# uc.net
KiCad netlist of a schematic drawn in Altium Designer
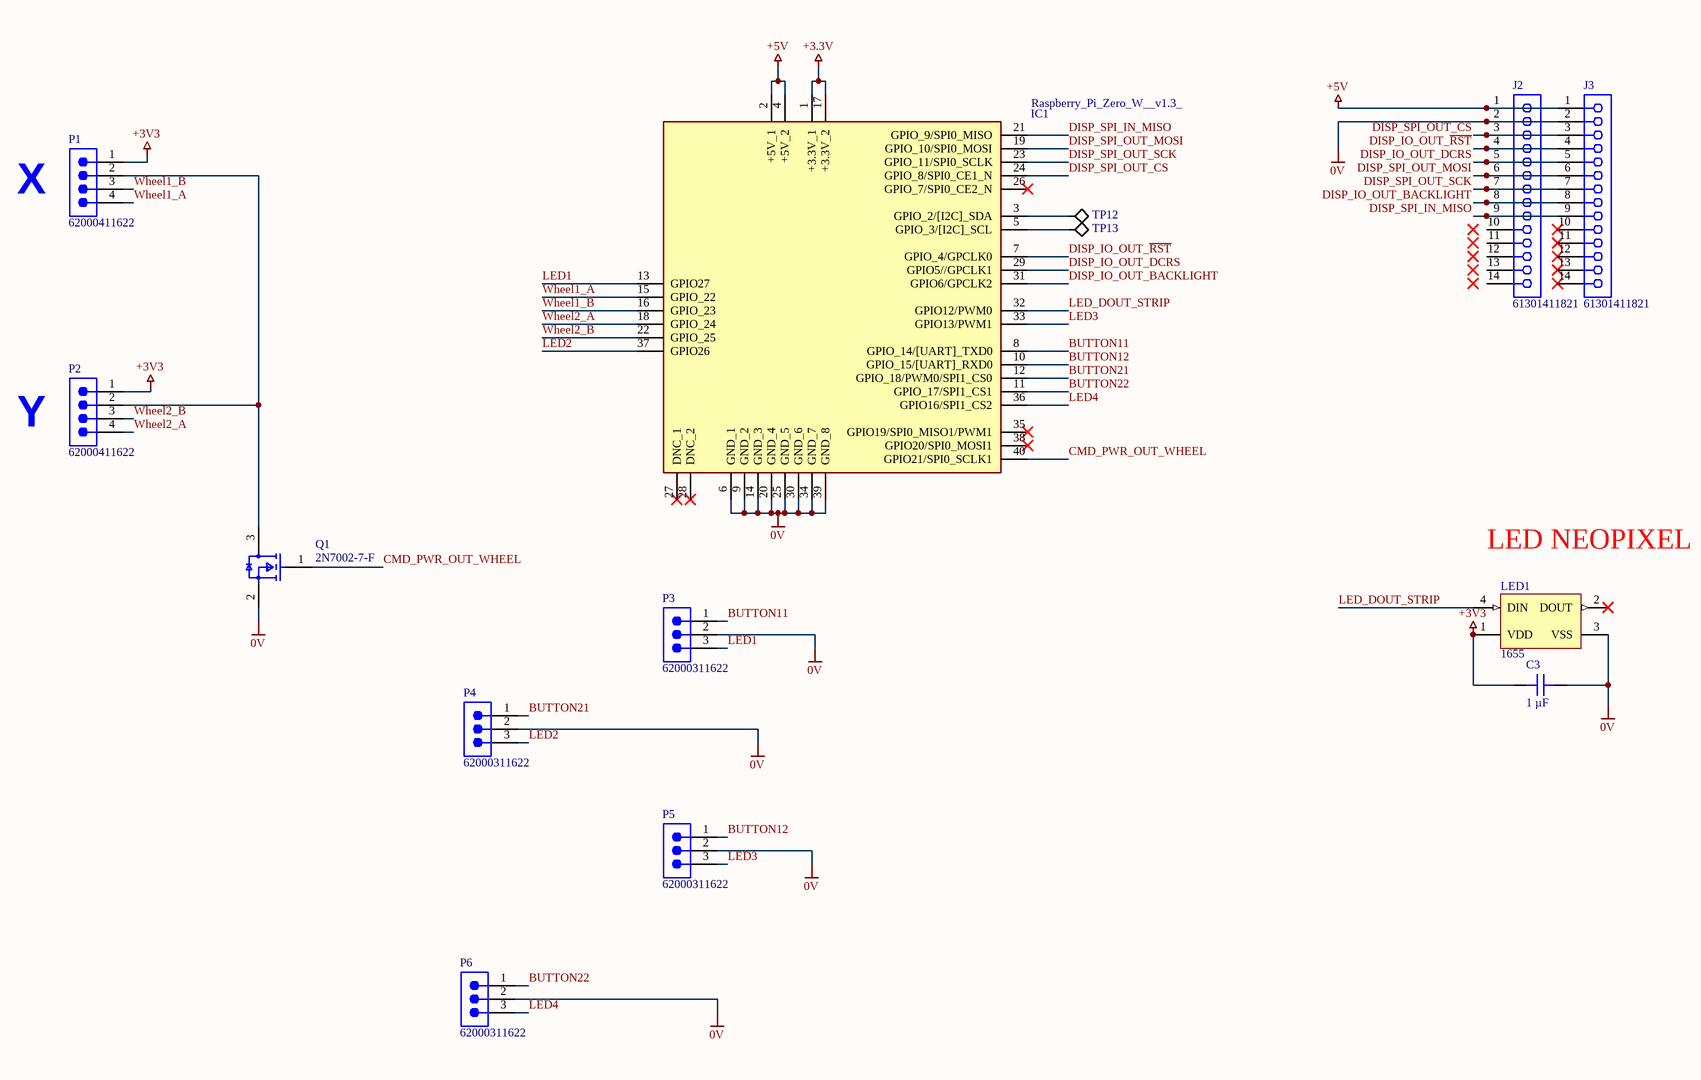
[diagram p0: uc.SchDoc]

(export (version "E")
  (design (tool "Eeschema 10.0.6"))
  (components
    (comp (ref "C3")
      (value "1 µF")
      (footprint "CAP 0603_1608")
      (description "CAP CER 1UF 16V X7R 0603")
      (fields
        (field (name "PART NUMBER") "GCM188R71C105KA64J")
        (field (name "MANUFACTURER") "Murata Electronics")
      )
      (libsource (lib "Celestial Altium Library - altium_library") (part "Capacitor"))
    )
    (comp (ref "IC1")
      (value "Raspberry_Pi_Zero_W__v1.3_")
      (footprint "RaspberryPiZero2W")
      (description "Integrated Circuit")
      (fields (field (name "MANUFACTURER_PART_NUMBER") "Raspberry Pi Zero W (v1.3)"))
      (libsource (lib "epieno") (part "Raspberry_Pi_Zero_W__v1.3_"))
    )
    (comp (ref "J2")
      (value "61301411821")
      (footprint "61301411821")
      (libsource (lib "Altium Content Vault") (part "Header_Female_1R_14P"))
    )
    (comp (ref "J3")
      (value "61301411821")
      (footprint "61301411821")
      (libsource (lib "Altium Content Vault") (part "Header_Female_1R_14P"))
    )
    (comp (ref "LED1")
      (value "1655")
      (footprint "ADA-RGB-1655_V")
      (fields (field (name "MANUFACTURER") "Adafruit-Industries-LLC"))
      (libsource (lib "Altium Content Vault") (part "ADA-RGB-1655-4"))
    )
    (comp (ref "P1")
      (value "62000411622")
      (footprint "62000411622")
      (libsource (lib "Altium Content Vault") (part "Header_Male_1R_04P"))
    )
    (comp (ref "P2")
      (value "62000411622")
      (footprint "62000411622")
      (libsource (lib "Altium Content Vault") (part "Header_Male_1R_04P"))
    )
    (comp (ref "P3")
      (value "62000311622")
      (footprint "62000311622")
      (libsource (lib "Altium Content Vault") (part "Header_Male_1R_03P"))
    )
    (comp (ref "P4")
      (value "62000311622")
      (footprint "62000311622")
      (libsource (lib "Altium Content Vault") (part "Header_Male_1R_03P"))
    )
    (comp (ref "P5")
      (value "62000311622")
      (footprint "62000311622")
      (libsource (lib "Altium Content Vault") (part "Header_Male_1R_03P"))
    )
    (comp (ref "P6")
      (value "62000311622")
      (footprint "62000311622")
      (libsource (lib "Altium Content Vault") (part "Header_Male_1R_03P"))
    )
    (comp (ref "Q1")
      (value "2N7002-7-F")
      (footprint "FP-SOT23-MFG")
      (description "MOSFET N-CH 60V 115MA SOT23-3")
      (fields (field (name "VOLTAGE") "60V"))
      (libsource (lib "Altium Content Vault") (part "3b9c635fedb024a5347a57b145af9cc"))
    )
    (comp (ref "TP12")
      (value "Test Point")
      (footprint "TESTPOINT_ROUND_2.0MM")
      (libsource (lib "epieno") (part "TEST_POINT_2MM"))
    )
    (comp (ref "TP13")
      (value "Test Point")
      (footprint "TESTPOINT_ROUND_2.0MM")
      (libsource (lib "epieno") (part "TEST_POINT_2MM"))
    )
  )
  (nets
    (net (code "1") (name "+3.3V") (class "Default")
      (node (ref "IC1") (pin "1") (pinfunction "+3.3V_1_1") (pintype "passive"))
      (node (ref "IC1") (pin "17") (pinfunction "+3.3V_2_17") (pintype "passive"))
    )
    (net (code "2") (name "+3V3") (class "Default")
      (node (ref "C3") (pin "2") (pinfunction "2_2") (pintype "passive"))
      (node (ref "LED1") (pin "1") (pinfunction "VDD_1") (pintype "power_in"))
      (node (ref "P1") (pin "1") (pinfunction "1_1") (pintype "passive"))
      (node (ref "P2") (pin "1") (pinfunction "1_1") (pintype "passive"))
    )
    (net (code "3") (name "+5V") (class "Default")
      (node (ref "IC1") (pin "2") (pinfunction "+5V_1_2") (pintype "passive"))
      (node (ref "IC1") (pin "4") (pinfunction "+5V_2_4") (pintype "passive"))
      (node (ref "J2") (pin "1") (pinfunction "1_1") (pintype "passive"))
      (node (ref "J3") (pin "1") (pinfunction "1_1") (pintype "passive"))
    )
    (net (code "4") (name "/BUTTON11") (class "Default")
      (node (ref "IC1") (pin "8") (pinfunction "GPIO_14/[UART]_TXD0_8") (pintype "passive"))
      (node (ref "P3") (pin "1") (pinfunction "1_1") (pintype "passive"))
    )
    (net (code "5") (name "/BUTTON12") (class "Default")
      (node (ref "IC1") (pin "10") (pinfunction "GPIO_15/[UART]_RXD0_10") (pintype "passive"))
      (node (ref "P5") (pin "1") (pinfunction "1_1") (pintype "passive"))
    )
    (net (code "6") (name "/BUTTON21") (class "Default")
      (node (ref "IC1") (pin "12") (pinfunction "GPIO_18/PWM0/SPI1_CS0_12") (pintype "passive"))
      (node (ref "P4") (pin "1") (pinfunction "1_1") (pintype "passive"))
    )
    (net (code "7") (name "/BUTTON22") (class "Default")
      (node (ref "IC1") (pin "11") (pinfunction "GPIO_17/SPI1_CS1_11") (pintype "passive"))
      (node (ref "P6") (pin "1") (pinfunction "1_1") (pintype "passive"))
    )
    (net (code "8") (name "/CMD_PWR_OUT_WHEEL") (class "Default")
      (node (ref "IC1") (pin "40") (pinfunction "GPIO21/SPI0_SCLK1_40") (pintype "passive"))
      (node (ref "Q1") (pin "1") (pinfunction "G_1") (pintype "passive"))
    )
    (net (code "9") (name "/DISP_IO_OUT_BACKLIGHT") (class "Default")
      (node (ref "IC1") (pin "31") (pinfunction "GPIO6/GPCLK2_31") (pintype "passive"))
      (node (ref "J2") (pin "8") (pinfunction "8_8") (pintype "passive"))
      (node (ref "J3") (pin "8") (pinfunction "8_8") (pintype "passive"))
    )
    (net (code "10") (name "/DISP_IO_OUT_DCRS") (class "Default")
      (node (ref "IC1") (pin "29") (pinfunction "GPIO5//GPCLK1_29") (pintype "passive"))
      (node (ref "J2") (pin "5") (pinfunction "5_5") (pintype "passive"))
      (node (ref "J3") (pin "5") (pinfunction "5_5") (pintype "passive"))
    )
    (net (code "11") (name "/DISP_IO_OUT_~{RST}") (class "Default")
      (node (ref "IC1") (pin "7") (pinfunction "GPIO_4/GPCLK0_7") (pintype "passive"))
      (node (ref "J2") (pin "4") (pinfunction "4_4") (pintype "passive"))
      (node (ref "J3") (pin "4") (pinfunction "4_4") (pintype "passive"))
    )
    (net (code "12") (name "/DISP_SPI_IN_MISO") (class "Default")
      (node (ref "IC1") (pin "21") (pinfunction "GPIO_9/SPI0_MISO_21") (pintype "passive"))
      (node (ref "J2") (pin "9") (pinfunction "9_9") (pintype "passive"))
      (node (ref "J3") (pin "9") (pinfunction "9_9") (pintype "passive"))
    )
    (net (code "13") (name "/DISP_SPI_OUT_CS") (class "Default")
      (node (ref "IC1") (pin "24") (pinfunction "GPIO_8/SPI0_CE1_N_24") (pintype "passive"))
      (node (ref "J2") (pin "3") (pinfunction "3_3") (pintype "passive"))
      (node (ref "J3") (pin "3") (pinfunction "3_3") (pintype "passive"))
    )
    (net (code "14") (name "/DISP_SPI_OUT_MOSI") (class "Default")
      (node (ref "IC1") (pin "19") (pinfunction "GPIO_10/SPI0_MOSI_19") (pintype "passive"))
      (node (ref "J2") (pin "6") (pinfunction "6_6") (pintype "passive"))
      (node (ref "J3") (pin "6") (pinfunction "6_6") (pintype "passive"))
    )
    (net (code "15") (name "/DISP_SPI_OUT_SCK") (class "Default")
      (node (ref "IC1") (pin "23") (pinfunction "GPIO_11/SPI0_SCLK_23") (pintype "passive"))
      (node (ref "J2") (pin "7") (pinfunction "7_7") (pintype "passive"))
      (node (ref "J3") (pin "7") (pinfunction "7_7") (pintype "passive"))
    )
    (net (code "16") (name "/LED1") (class "Default")
      (node (ref "IC1") (pin "13") (pinfunction "GPIO27_13") (pintype "passive"))
      (node (ref "P3") (pin "3") (pinfunction "3_3") (pintype "passive"))
    )
    (net (code "17") (name "/LED2") (class "Default")
      (node (ref "IC1") (pin "37") (pinfunction "GPIO26_37") (pintype "passive"))
      (node (ref "P4") (pin "3") (pinfunction "3_3") (pintype "passive"))
    )
    (net (code "18") (name "/LED3") (class "Default")
      (node (ref "IC1") (pin "33") (pinfunction "GPIO13/PWM1_33") (pintype "passive"))
      (node (ref "P5") (pin "3") (pinfunction "3_3") (pintype "passive"))
    )
    (net (code "19") (name "/LED4") (class "Default")
      (node (ref "IC1") (pin "36") (pinfunction "GPIO16/SPI1_CS2_36") (pintype "passive"))
      (node (ref "P6") (pin "3") (pinfunction "3_3") (pintype "passive"))
    )
    (net (code "20") (name "/LED_DOUT_STRIP") (class "Default")
      (node (ref "IC1") (pin "32") (pinfunction "GPIO12/PWM0_32") (pintype "passive"))
      (node (ref "LED1") (pin "4") (pinfunction "DIN_4") (pintype "input"))
    )
    (net (code "21") (name "/Wheel1_A") (class "Default")
      (node (ref "IC1") (pin "15") (pinfunction "GPIO_22_15") (pintype "passive"))
      (node (ref "P1") (pin "4") (pinfunction "4_4") (pintype "passive"))
    )
    (net (code "22") (name "/Wheel1_B") (class "Default")
      (node (ref "IC1") (pin "16") (pinfunction "GPIO_23_16") (pintype "passive"))
      (node (ref "P1") (pin "3") (pinfunction "3_3") (pintype "passive"))
    )
    (net (code "23") (name "/Wheel2_A") (class "Default")
      (node (ref "IC1") (pin "18") (pinfunction "GPIO_24_18") (pintype "passive"))
      (node (ref "P2") (pin "4") (pinfunction "4_4") (pintype "passive"))
    )
    (net (code "24") (name "/Wheel2_B") (class "Default")
      (node (ref "IC1") (pin "22") (pinfunction "GPIO_25_22") (pintype "passive"))
      (node (ref "P2") (pin "3") (pinfunction "3_3") (pintype "passive"))
    )
    (net (code "25") (name "0V") (class "Default")
      (node (ref "C3") (pin "1") (pinfunction "1_1") (pintype "passive"))
      (node (ref "IC1") (pin "14") (pinfunction "GND_3_14") (pintype "passive"))
      (node (ref "IC1") (pin "20") (pinfunction "GND_4_20") (pintype "passive"))
      (node (ref "IC1") (pin "25") (pinfunction "GND_5_25") (pintype "passive"))
      (node (ref "IC1") (pin "30") (pinfunction "GND_6_30") (pintype "passive"))
      (node (ref "IC1") (pin "34") (pinfunction "GND_7_34") (pintype "passive"))
      (node (ref "IC1") (pin "39") (pinfunction "GND_8_39") (pintype "passive"))
      (node (ref "IC1") (pin "6") (pinfunction "GND_1_6") (pintype "passive"))
      (node (ref "IC1") (pin "9") (pinfunction "GND_2_9") (pintype "passive"))
      (node (ref "J2") (pin "2") (pinfunction "2_2") (pintype "passive"))
      (node (ref "J3") (pin "2") (pinfunction "2_2") (pintype "passive"))
      (node (ref "LED1") (pin "3") (pinfunction "VSS_3") (pintype "power_in"))
      (node (ref "P3") (pin "2") (pinfunction "2_2") (pintype "passive"))
      (node (ref "P4") (pin "2") (pinfunction "2_2") (pintype "passive"))
      (node (ref "P5") (pin "2") (pinfunction "2_2") (pintype "passive"))
      (node (ref "P6") (pin "2") (pinfunction "2_2") (pintype "passive"))
      (node (ref "Q1") (pin "2") (pinfunction "S_2") (pintype "passive"))
    )
    (net (code "26") (name "Net-(IC1-GPIO_2{slash}[I2C]_SDA)") (class "Default")
      (node (ref "IC1") (pin "3") (pinfunction "GPIO_2/[I2C]_SDA_3") (pintype "passive"))
      (node (ref "TP12") (pin "1") (pinfunction "TP_1") (pintype "passive"))
    )
    (net (code "27") (name "Net-(IC1-GPIO_3{slash}[I2C]_SCL)") (class "Default")
      (node (ref "IC1") (pin "5") (pinfunction "GPIO_3/[I2C]_SCL_5") (pintype "passive"))
      (node (ref "TP13") (pin "1") (pinfunction "TP_1") (pintype "passive"))
    )
    (net (code "28") (name "Net-(Q1-D)") (class "Default")
      (node (ref "P1") (pin "2") (pinfunction "2_2") (pintype "passive"))
      (node (ref "P2") (pin "2") (pinfunction "2_2") (pintype "passive"))
      (node (ref "Q1") (pin "3") (pinfunction "D_3") (pintype "passive"))
    )
    (net (code "29") (name "unconnected-(IC1-DNC_1-Pad27)") (class "Default")
      (node (ref "IC1") (pin "27") (pinfunction "DNC_1_27") (pintype "passive+no_connect"))
    )
    (net (code "30") (name "unconnected-(IC1-DNC_2-Pad28)") (class "Default")
      (node (ref "IC1") (pin "28") (pinfunction "DNC_2_28") (pintype "passive+no_connect"))
    )
    (net (code "31") (name "unconnected-(IC1-GPIO19{slash}SPI0_MISO1{slash}PWM1-Pad35)") (class "Default")
      (node (ref "IC1") (pin "35") (pinfunction "GPIO19/SPI0_MISO1/PWM1_35") (pintype "passive+no_connect"))
    )
    (net (code "32") (name "unconnected-(IC1-GPIO20{slash}SPI0_MOSI1-Pad38)") (class "Default")
      (node (ref "IC1") (pin "38") (pinfunction "GPIO20/SPI0_MOSI1_38") (pintype "passive+no_connect"))
    )
    (net (code "33") (name "unconnected-(IC1-GPIO_7{slash}SPI0_CE2_N-Pad26)") (class "Default")
      (node (ref "IC1") (pin "26") (pinfunction "GPIO_7/SPI0_CE2_N_26") (pintype "passive+no_connect"))
    )
    (net (code "34") (name "unconnected-(J2-Pad10)") (class "Default")
      (node (ref "J2") (pin "10") (pinfunction "10_10") (pintype "passive"))
    )
    (net (code "35") (name "unconnected-(J2-Pad11)") (class "Default")
      (node (ref "J2") (pin "11") (pinfunction "11_11") (pintype "passive"))
    )
    (net (code "36") (name "unconnected-(J2-Pad12)") (class "Default")
      (node (ref "J2") (pin "12") (pinfunction "12_12") (pintype "passive"))
    )
    (net (code "37") (name "unconnected-(J2-Pad13)") (class "Default")
      (node (ref "J2") (pin "13") (pinfunction "13_13") (pintype "passive"))
    )
    (net (code "38") (name "unconnected-(J2-Pad14)") (class "Default")
      (node (ref "J2") (pin "14") (pinfunction "14_14") (pintype "passive"))
    )
    (net (code "39") (name "unconnected-(J3-Pad10)") (class "Default")
      (node (ref "J3") (pin "10") (pinfunction "10_10") (pintype "passive+no_connect"))
    )
    (net (code "40") (name "unconnected-(J3-Pad11)") (class "Default")
      (node (ref "J3") (pin "11") (pinfunction "11_11") (pintype "passive+no_connect"))
    )
    (net (code "41") (name "unconnected-(J3-Pad12)") (class "Default")
      (node (ref "J3") (pin "12") (pinfunction "12_12") (pintype "passive+no_connect"))
    )
    (net (code "42") (name "unconnected-(J3-Pad13)") (class "Default")
      (node (ref "J3") (pin "13") (pinfunction "13_13") (pintype "passive+no_connect"))
    )
    (net (code "43") (name "unconnected-(J3-Pad14)") (class "Default")
      (node (ref "J3") (pin "14") (pinfunction "14_14") (pintype "passive+no_connect"))
    )
    (net (code "44") (name "unconnected-(LED1-DOUT-Pad2)") (class "Default")
      (node (ref "LED1") (pin "2") (pinfunction "DOUT_2") (pintype "output+no_connect"))
    )
  )
)
